# ziffy_board_v3.net
KiCad netlist of a schematic drawn in EAGLE
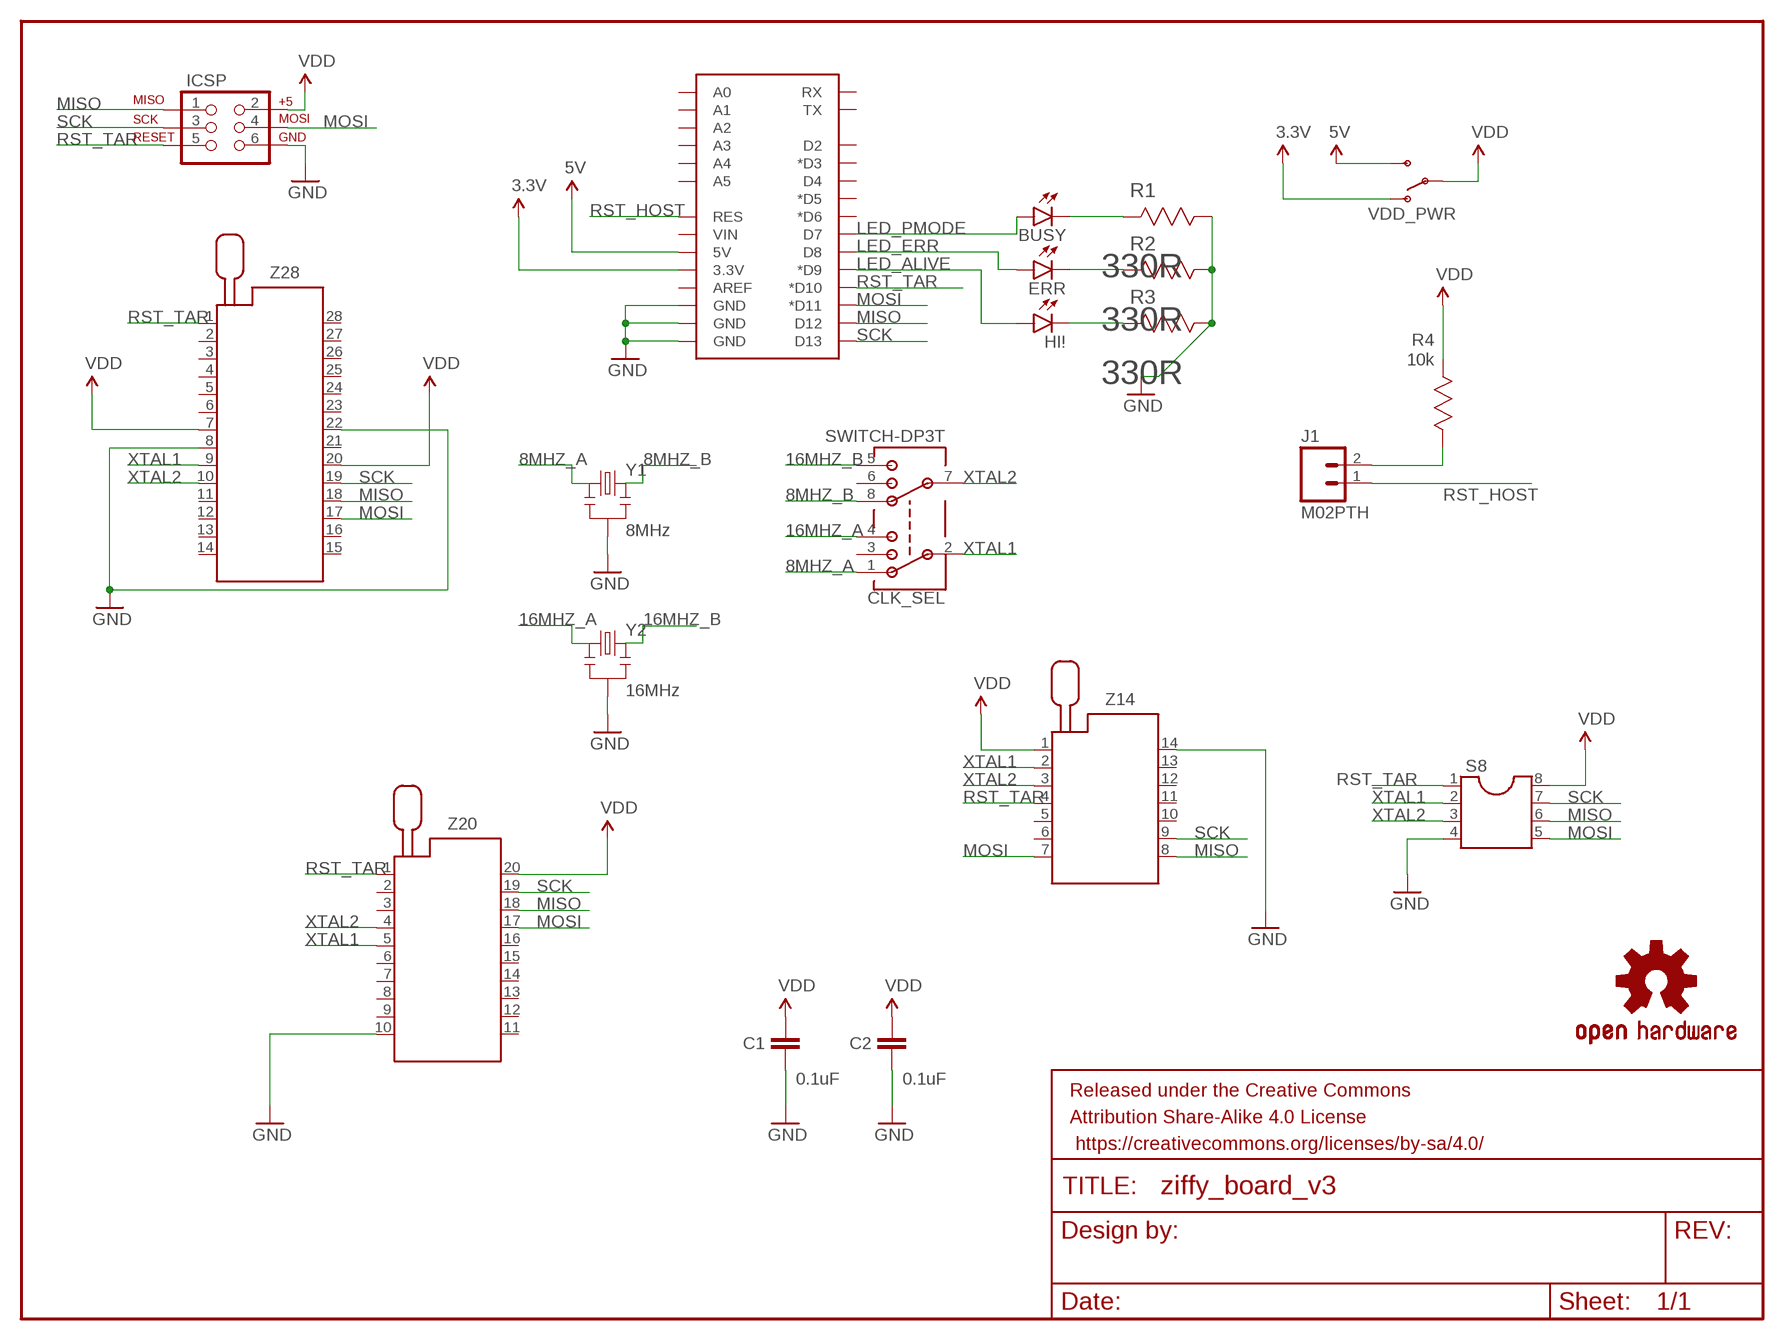
[diagram p0: schematic, sheet 1]

(export (version "E")
  (design (tool "Eeschema 10.0.6"))
  (components
    (comp (ref "BUSY")
      (value "YELLOW")
      (footprint "eagle-import:LED3MM")
      (libsource (lib "eagle-import") (part "LED3MM"))
    )
    (comp (ref "C1")
      (value "0.1uF")
      (footprint "eagle-import:CAP-PTH-SMALL2")
      (libsource (lib "eagle-import") (part "CAPPTH2"))
    )
    (comp (ref "C2")
      (value "0.1uF")
      (footprint "eagle-import:CAP-PTH-SMALL2")
      (libsource (lib "eagle-import") (part "CAPPTH2"))
    )
    (comp (ref "CLK_SEL")
      (value "SWITCH-DP3T")
      (footprint "eagle-import:SWITCH-DP3T")
      (libsource (lib "eagle-import") (part "SWITCH-DP3T"))
    )
    (comp (ref "ERR")
      (value "RED")
      (footprint "eagle-import:LED3MM")
      (libsource (lib "eagle-import") (part "LED3MM"))
    )
    (comp (ref "FRAME1")
      (value "FRAME-LETTER")
      (footprint "eagle-import:CREATIVE_COMMONS")
      (libsource (lib "eagle-import") (part "FRAME-LETTER"))
    )
    (comp (ref "HI!")
      (value "GREEN")
      (footprint "eagle-import:LED3MM")
      (libsource (lib "eagle-import") (part "LED3MM"))
    )
    (comp (ref "ICSP")
      (value "AVR_SPI_PRG_6PTH")
      (footprint "eagle-import:2X3")
      (libsource (lib "eagle-import") (part "AVR_SPI_PRG_6PTH"))
    )
    (comp (ref "J1")
      (value "M02PTH")
      (footprint "eagle-import:1X02")
      (libsource (lib "eagle-import") (part "M02PTH"))
    )
    (comp (ref "LOGO2")
      (value "OSHW-LOGOS")
      (footprint "eagle-import:OSHW-LOGO-S")
      (libsource (lib "eagle-import") (part "OSHW-LOGOS"))
    )
    (comp (ref "R1")
      (value "330R")
      (footprint "eagle-import:AXIAL-0.2")
      (libsource (lib "eagle-import") (part "RESISTOR_PTH_0.2"))
    )
    (comp (ref "R2")
      (value "330R")
      (footprint "eagle-import:AXIAL-0.2")
      (libsource (lib "eagle-import") (part "RESISTOR_PTH_0.2"))
    )
    (comp (ref "R3")
      (value "330R")
      (footprint "eagle-import:AXIAL-0.2")
      (libsource (lib "eagle-import") (part "RESISTOR_PTH_0.2"))
    )
    (comp (ref "R4")
      (value "10k")
      (footprint "eagle-import:AXIAL-0.2")
      (libsource (lib "eagle-import") (part "RESISTOR_PTH_0.2"))
    )
    (comp (ref "S8")
      (value "DIPSHIT")
      (footprint "eagle-import:DIL08")
      (libsource (lib "eagle-import") (part "DIL8"))
    )
    (comp (ref "U$1")
      (value "ARDUINO_SHIELDOUTLINE_NOHOLES")
      (footprint "eagle-import:ARDUINO_SHIELD_OUTLINE_NOHOLES")
      (libsource (lib "eagle-import") (part "ARDUINO_SHIELDOUTLINE_NOHOLES"))
    )
    (comp (ref "VDD_PWR")
      (value "SPDT")
      (footprint "eagle-import:SWITCH-SPDT")
      (libsource (lib "eagle-import") (part "SWITCH-SPDTPTH"))
    )
    (comp (ref "Y1")
      (value "8MHz")
      (footprint "eagle-import:RESONATOR-PTH")
      (libsource (lib "eagle-import") (part "RESONATORPTH"))
    )
    (comp (ref "Y2")
      (value "16MHz")
      (footprint "eagle-import:RESONATOR-PTH")
      (libsource (lib "eagle-import") (part "RESONATORPTH"))
    )
    (comp (ref "Z14")
      (value "ZIF14")
      (footprint "eagle-import:ZIF14")
      (fields (field (name "MF") "3M") (field (name "MPN") "214-3339-00-0602J"))
      (libsource (lib "eagle-import") (part "ZIF14"))
    )
    (comp (ref "Z20")
      (value "ZIF20")
      (footprint "eagle-import:ZIF20")
      (fields (field (name "MF") "3M") (field (name "MPN") "220-3342-00-0602J"))
      (libsource (lib "eagle-import") (part "ZIF20"))
    )
    (comp (ref "Z28")
      (value "ZIF28")
      (footprint "eagle-import:ZIF28")
      (libsource (lib "eagle-import") (part "ZIF28"))
    )
  )
  (nets
    (net (code "1") (name "/8MHZ_A") (class "Default")
      (node (ref "CLK_SEL") (pin "1") (pinfunction "1_1") (pintype "bidirectional"))
      (node (ref "Y1") (pin "1") (pinfunction "1_1") (pintype "passive"))
    )
    (net (code "2") (name "/8MHZ_B") (class "Default")
      (node (ref "CLK_SEL") (pin "8") (pinfunction "8_8") (pintype "bidirectional"))
      (node (ref "Y1") (pin "3") (pinfunction "3_3") (pintype "passive"))
    )
    (net (code "3") (name "/16MHZ_A") (class "Default")
      (node (ref "CLK_SEL") (pin "4") (pinfunction "4_4") (pintype "bidirectional"))
      (node (ref "Y2") (pin "1") (pinfunction "1_1") (pintype "passive"))
    )
    (net (code "4") (name "/16MHZ_B") (class "Default")
      (node (ref "CLK_SEL") (pin "5") (pinfunction "5_5") (pintype "bidirectional"))
      (node (ref "Y2") (pin "3") (pinfunction "3_3") (pintype "passive"))
    )
    (net (code "5") (name "/LED_ALIVE") (class "Default")
      (node (ref "HI!") (pin "A") (pinfunction "A_A") (pintype "passive"))
      (node (ref "U$1") (pin "D9") (pinfunction "*D9_D9") (pintype "bidirectional"))
    )
    (net (code "6") (name "/LED_ERR") (class "Default")
      (node (ref "ERR") (pin "A") (pinfunction "A_A") (pintype "passive"))
      (node (ref "U$1") (pin "D8") (pinfunction "D8_D8") (pintype "bidirectional"))
    )
    (net (code "7") (name "/LED_PMODE") (class "Default")
      (node (ref "BUSY") (pin "A") (pinfunction "A_A") (pintype "passive"))
      (node (ref "U$1") (pin "D7") (pinfunction "D7_D7") (pintype "bidirectional"))
    )
    (net (code "8") (name "/MISO") (class "Default")
      (node (ref "ICSP") (pin "1") (pinfunction "1_1") (pintype "passive"))
      (node (ref "S8") (pin "6") (pinfunction "6_6") (pintype "passive"))
      (node (ref "U$1") (pin "D12") (pinfunction "D12_D12") (pintype "bidirectional"))
      (node (ref "Z14") (pin "8") (pinfunction "8_8") (pintype "passive"))
      (node (ref "Z20") (pin "18") (pinfunction "18_18") (pintype "passive"))
      (node (ref "Z28") (pin "18") (pinfunction "18_18") (pintype "passive"))
    )
    (net (code "9") (name "/MOSI") (class "Default")
      (node (ref "ICSP") (pin "4") (pinfunction "4_4") (pintype "passive"))
      (node (ref "S8") (pin "5") (pinfunction "5_5") (pintype "passive"))
      (node (ref "U$1") (pin "D11") (pinfunction "*D11_D11") (pintype "bidirectional"))
      (node (ref "Z14") (pin "7") (pinfunction "7_7") (pintype "passive"))
      (node (ref "Z20") (pin "17") (pinfunction "17_17") (pintype "passive"))
      (node (ref "Z28") (pin "17") (pinfunction "17_17") (pintype "passive"))
    )
    (net (code "10") (name "/RST_HOST") (class "Default")
      (node (ref "J1") (pin "1") (pinfunction "1_1") (pintype "passive"))
      (node (ref "U$1") (pin "RES") (pinfunction "RES_RES") (pintype "bidirectional"))
    )
    (net (code "11") (name "/RST_TAR") (class "Default")
      (node (ref "ICSP") (pin "5") (pinfunction "5_5") (pintype "passive"))
      (node (ref "S8") (pin "1") (pinfunction "1_1") (pintype "passive"))
      (node (ref "U$1") (pin "D10") (pinfunction "*D10_D10") (pintype "bidirectional"))
      (node (ref "Z14") (pin "4") (pinfunction "4_4") (pintype "passive"))
      (node (ref "Z20") (pin "1") (pinfunction "1_1") (pintype "passive"))
      (node (ref "Z28") (pin "1") (pinfunction "1_1") (pintype "passive"))
    )
    (net (code "12") (name "/SCK") (class "Default")
      (node (ref "ICSP") (pin "3") (pinfunction "3_3") (pintype "passive"))
      (node (ref "S8") (pin "7") (pinfunction "7_7") (pintype "passive"))
      (node (ref "U$1") (pin "D13") (pinfunction "D13_D13") (pintype "bidirectional"))
      (node (ref "Z14") (pin "9") (pinfunction "9_9") (pintype "passive"))
      (node (ref "Z20") (pin "19") (pinfunction "19_19") (pintype "passive"))
      (node (ref "Z28") (pin "19") (pinfunction "19_19") (pintype "passive"))
    )
    (net (code "13") (name "/XTAL1") (class "Default")
      (node (ref "CLK_SEL") (pin "2") (pinfunction "2_2") (pintype "bidirectional"))
      (node (ref "S8") (pin "2") (pinfunction "2_2") (pintype "passive"))
      (node (ref "Z14") (pin "2") (pinfunction "2_2") (pintype "passive"))
      (node (ref "Z20") (pin "5") (pinfunction "5_5") (pintype "passive"))
      (node (ref "Z28") (pin "9") (pinfunction "9_9") (pintype "passive"))
    )
    (net (code "14") (name "/XTAL2") (class "Default")
      (node (ref "CLK_SEL") (pin "7") (pinfunction "7_7") (pintype "bidirectional"))
      (node (ref "S8") (pin "3") (pinfunction "3_3") (pintype "passive"))
      (node (ref "Z14") (pin "3") (pinfunction "3_3") (pintype "passive"))
      (node (ref "Z20") (pin "4") (pinfunction "4_4") (pintype "passive"))
      (node (ref "Z28") (pin "10") (pinfunction "10_10") (pintype "passive"))
    )
    (net (code "15") (name "3.3V") (class "Default")
      (node (ref "U$1") (pin "3.3V") (pinfunction "3.3V_3.3V") (pintype "bidirectional"))
      (node (ref "VDD_PWR") (pin "1") (pinfunction "O_1") (pintype "passive"))
    )
    (net (code "16") (name "5V") (class "Default")
      (node (ref "U$1") (pin "5V") (pinfunction "5V_5V") (pintype "bidirectional"))
      (node (ref "VDD_PWR") (pin "3") (pinfunction "S_3") (pintype "passive"))
    )
    (net (code "17") (name "GND") (class "Default")
      (node (ref "C1") (pin "2") (pinfunction "2_2") (pintype "passive"))
      (node (ref "C2") (pin "2") (pinfunction "2_2") (pintype "passive"))
      (node (ref "ICSP") (pin "6") (pinfunction "6_6") (pintype "passive"))
      (node (ref "R1") (pin "P$1") (pinfunction "2_P$1") (pintype "passive"))
      (node (ref "R2") (pin "P$1") (pinfunction "2_P$1") (pintype "passive"))
      (node (ref "R3") (pin "P$1") (pinfunction "2_P$1") (pintype "passive"))
      (node (ref "S8") (pin "4") (pinfunction "4_4") (pintype "passive"))
      (node (ref "U$1") (pin "GND@0") (pinfunction "GND_GND@0") (pintype "bidirectional"))
      (node (ref "U$1") (pin "GND@1") (pinfunction "GND_GND@1") (pintype "bidirectional"))
      (node (ref "U$1") (pin "GND@2") (pinfunction "GND_GND@2") (pintype "bidirectional"))
      (node (ref "Y1") (pin "2") (pinfunction "2_2") (pintype "passive"))
      (node (ref "Y2") (pin "2") (pinfunction "2_2") (pintype "passive"))
      (node (ref "Z14") (pin "14") (pinfunction "14_14") (pintype "passive"))
      (node (ref "Z20") (pin "10") (pinfunction "10_10") (pintype "passive"))
      (node (ref "Z28") (pin "22") (pinfunction "22_22") (pintype "passive"))
      (node (ref "Z28") (pin "8") (pinfunction "8_8") (pintype "passive"))
    )
    (net (code "18") (name "Net-(BUSY-C)") (class "Default")
      (node (ref "BUSY") (pin "K") (pinfunction "C_K") (pintype "passive"))
      (node (ref "R1") (pin "P$2") (pinfunction "1_P$2") (pintype "passive"))
    )
    (net (code "19") (name "Net-(ERR-C)") (class "Default")
      (node (ref "ERR") (pin "K") (pinfunction "C_K") (pintype "passive"))
      (node (ref "R2") (pin "P$2") (pinfunction "1_P$2") (pintype "passive"))
    )
    (net (code "20") (name "Net-(HI!-C)") (class "Default")
      (node (ref "HI!") (pin "K") (pinfunction "C_K") (pintype "passive"))
      (node (ref "R3") (pin "P$2") (pinfunction "1_P$2") (pintype "passive"))
    )
    (net (code "21") (name "Net-(R4-2)") (class "Default")
      (node (ref "J1") (pin "2") (pinfunction "2_2") (pintype "passive"))
      (node (ref "R4") (pin "P$1") (pinfunction "2_P$1") (pintype "passive"))
    )
    (net (code "22") (name "VDD") (class "Default")
      (node (ref "C1") (pin "1") (pinfunction "1_1") (pintype "passive"))
      (node (ref "C2") (pin "1") (pinfunction "1_1") (pintype "passive"))
      (node (ref "ICSP") (pin "2") (pinfunction "2_2") (pintype "passive"))
      (node (ref "R4") (pin "P$2") (pinfunction "1_P$2") (pintype "passive"))
      (node (ref "S8") (pin "8") (pinfunction "8_8") (pintype "passive"))
      (node (ref "VDD_PWR") (pin "2") (pinfunction "P_2") (pintype "passive"))
      (node (ref "Z14") (pin "1") (pinfunction "1_1") (pintype "passive"))
      (node (ref "Z20") (pin "20") (pinfunction "20_20") (pintype "passive"))
      (node (ref "Z28") (pin "20") (pinfunction "20_20") (pintype "passive"))
      (node (ref "Z28") (pin "7") (pinfunction "7_7") (pintype "passive"))
    )
    (net (code "23") (name "unconnected-(CLK_SEL-Pad3)") (class "Default")
      (node (ref "CLK_SEL") (pin "3") (pinfunction "3_3") (pintype "bidirectional"))
    )
    (net (code "24") (name "unconnected-(CLK_SEL-Pad6)") (class "Default")
      (node (ref "CLK_SEL") (pin "6") (pinfunction "6_6") (pintype "bidirectional"))
    )
    (net (code "25") (name "unconnected-(U$1-*D3-PadD3)") (class "Default")
      (node (ref "U$1") (pin "D3") (pinfunction "*D3_D3") (pintype "bidirectional"))
    )
    (net (code "26") (name "unconnected-(U$1-*D5-PadD5)") (class "Default")
      (node (ref "U$1") (pin "D5") (pinfunction "*D5_D5") (pintype "bidirectional"))
    )
    (net (code "27") (name "unconnected-(U$1-*D6-PadD6)") (class "Default")
      (node (ref "U$1") (pin "D6") (pinfunction "*D6_D6") (pintype "bidirectional"))
    )
    (net (code "28") (name "unconnected-(U$1-PadA0)") (class "Default")
      (node (ref "U$1") (pin "A0") (pinfunction "A0_A0") (pintype "bidirectional"))
    )
    (net (code "29") (name "unconnected-(U$1-PadA1)") (class "Default")
      (node (ref "U$1") (pin "A1") (pinfunction "A1_A1") (pintype "bidirectional"))
    )
    (net (code "30") (name "unconnected-(U$1-PadA2)") (class "Default")
      (node (ref "U$1") (pin "A2") (pinfunction "A2_A2") (pintype "bidirectional"))
    )
    (net (code "31") (name "unconnected-(U$1-PadA3)") (class "Default")
      (node (ref "U$1") (pin "A3") (pinfunction "A3_A3") (pintype "bidirectional"))
    )
    (net (code "32") (name "unconnected-(U$1-PadA4)") (class "Default")
      (node (ref "U$1") (pin "A4") (pinfunction "A4_A4") (pintype "bidirectional"))
    )
    (net (code "33") (name "unconnected-(U$1-PadA5)") (class "Default")
      (node (ref "U$1") (pin "A5") (pinfunction "A5_A5") (pintype "bidirectional"))
    )
    (net (code "34") (name "unconnected-(U$1-PadAREF)") (class "Default")
      (node (ref "U$1") (pin "AREF") (pinfunction "AREF_AREF") (pintype "bidirectional"))
    )
    (net (code "35") (name "unconnected-(U$1-PadD2)") (class "Default")
      (node (ref "U$1") (pin "D2") (pinfunction "D2_D2") (pintype "bidirectional"))
    )
    (net (code "36") (name "unconnected-(U$1-PadD4)") (class "Default")
      (node (ref "U$1") (pin "D4") (pinfunction "D4_D4") (pintype "bidirectional"))
    )
    (net (code "37") (name "unconnected-(U$1-PadRX)") (class "Default")
      (node (ref "U$1") (pin "RX") (pinfunction "RX_RX") (pintype "bidirectional"))
    )
    (net (code "38") (name "unconnected-(U$1-PadTX)") (class "Default")
      (node (ref "U$1") (pin "TX") (pinfunction "TX_TX") (pintype "bidirectional"))
    )
    (net (code "39") (name "unconnected-(U$1-PadVIN)") (class "Default")
      (node (ref "U$1") (pin "VIN") (pinfunction "VIN_VIN") (pintype "bidirectional"))
    )
    (net (code "40") (name "unconnected-(Z14-Pad5)") (class "Default")
      (node (ref "Z14") (pin "5") (pinfunction "5_5") (pintype "passive"))
    )
    (net (code "41") (name "unconnected-(Z14-Pad6)") (class "Default")
      (node (ref "Z14") (pin "6") (pinfunction "6_6") (pintype "passive"))
    )
    (net (code "42") (name "unconnected-(Z14-Pad10)") (class "Default")
      (node (ref "Z14") (pin "10") (pinfunction "10_10") (pintype "passive"))
    )
    (net (code "43") (name "unconnected-(Z14-Pad11)") (class "Default")
      (node (ref "Z14") (pin "11") (pinfunction "11_11") (pintype "passive"))
    )
    (net (code "44") (name "unconnected-(Z14-Pad12)") (class "Default")
      (node (ref "Z14") (pin "12") (pinfunction "12_12") (pintype "passive"))
    )
    (net (code "45") (name "unconnected-(Z14-Pad13)") (class "Default")
      (node (ref "Z14") (pin "13") (pinfunction "13_13") (pintype "passive"))
    )
    (net (code "46") (name "unconnected-(Z20-Pad2)") (class "Default")
      (node (ref "Z20") (pin "2") (pinfunction "2_2") (pintype "passive"))
    )
    (net (code "47") (name "unconnected-(Z20-Pad3)") (class "Default")
      (node (ref "Z20") (pin "3") (pinfunction "3_3") (pintype "passive"))
    )
    (net (code "48") (name "unconnected-(Z20-Pad6)") (class "Default")
      (node (ref "Z20") (pin "6") (pinfunction "6_6") (pintype "passive"))
    )
    (net (code "49") (name "unconnected-(Z20-Pad7)") (class "Default")
      (node (ref "Z20") (pin "7") (pinfunction "7_7") (pintype "passive"))
    )
    (net (code "50") (name "unconnected-(Z20-Pad8)") (class "Default")
      (node (ref "Z20") (pin "8") (pinfunction "8_8") (pintype "passive"))
    )
    (net (code "51") (name "unconnected-(Z20-Pad9)") (class "Default")
      (node (ref "Z20") (pin "9") (pinfunction "9_9") (pintype "passive"))
    )
    (net (code "52") (name "unconnected-(Z20-Pad11)") (class "Default")
      (node (ref "Z20") (pin "11") (pinfunction "11_11") (pintype "passive"))
    )
    (net (code "53") (name "unconnected-(Z20-Pad12)") (class "Default")
      (node (ref "Z20") (pin "12") (pinfunction "12_12") (pintype "passive"))
    )
    (net (code "54") (name "unconnected-(Z20-Pad13)") (class "Default")
      (node (ref "Z20") (pin "13") (pinfunction "13_13") (pintype "passive"))
    )
    (net (code "55") (name "unconnected-(Z20-Pad14)") (class "Default")
      (node (ref "Z20") (pin "14") (pinfunction "14_14") (pintype "passive"))
    )
    (net (code "56") (name "unconnected-(Z20-Pad15)") (class "Default")
      (node (ref "Z20") (pin "15") (pinfunction "15_15") (pintype "passive"))
    )
    (net (code "57") (name "unconnected-(Z20-Pad16)") (class "Default")
      (node (ref "Z20") (pin "16") (pinfunction "16_16") (pintype "passive"))
    )
    (net (code "58") (name "unconnected-(Z28-Pad2)") (class "Default")
      (node (ref "Z28") (pin "2") (pinfunction "2_2") (pintype "passive"))
    )
    (net (code "59") (name "unconnected-(Z28-Pad3)") (class "Default")
      (node (ref "Z28") (pin "3") (pinfunction "3_3") (pintype "passive"))
    )
    (net (code "60") (name "unconnected-(Z28-Pad4)") (class "Default")
      (node (ref "Z28") (pin "4") (pinfunction "4_4") (pintype "passive"))
    )
    (net (code "61") (name "unconnected-(Z28-Pad5)") (class "Default")
      (node (ref "Z28") (pin "5") (pinfunction "5_5") (pintype "passive"))
    )
    (net (code "62") (name "unconnected-(Z28-Pad6)") (class "Default")
      (node (ref "Z28") (pin "6") (pinfunction "6_6") (pintype "passive"))
    )
    (net (code "63") (name "unconnected-(Z28-Pad11)") (class "Default")
      (node (ref "Z28") (pin "11") (pinfunction "11_11") (pintype "passive"))
    )
    (net (code "64") (name "unconnected-(Z28-Pad12)") (class "Default")
      (node (ref "Z28") (pin "12") (pinfunction "12_12") (pintype "passive"))
    )
    (net (code "65") (name "unconnected-(Z28-Pad13)") (class "Default")
      (node (ref "Z28") (pin "13") (pinfunction "13_13") (pintype "passive"))
    )
    (net (code "66") (name "unconnected-(Z28-Pad14)") (class "Default")
      (node (ref "Z28") (pin "14") (pinfunction "14_14") (pintype "passive"))
    )
    (net (code "67") (name "unconnected-(Z28-Pad15)") (class "Default")
      (node (ref "Z28") (pin "15") (pinfunction "15_15") (pintype "passive"))
    )
    (net (code "68") (name "unconnected-(Z28-Pad16)") (class "Default")
      (node (ref "Z28") (pin "16") (pinfunction "16_16") (pintype "passive"))
    )
    (net (code "69") (name "unconnected-(Z28-Pad21)") (class "Default")
      (node (ref "Z28") (pin "21") (pinfunction "21_21") (pintype "passive"))
    )
    (net (code "70") (name "unconnected-(Z28-Pad23)") (class "Default")
      (node (ref "Z28") (pin "23") (pinfunction "23_23") (pintype "passive"))
    )
    (net (code "71") (name "unconnected-(Z28-Pad24)") (class "Default")
      (node (ref "Z28") (pin "24") (pinfunction "24_24") (pintype "passive"))
    )
    (net (code "72") (name "unconnected-(Z28-Pad25)") (class "Default")
      (node (ref "Z28") (pin "25") (pinfunction "25_25") (pintype "passive"))
    )
    (net (code "73") (name "unconnected-(Z28-Pad26)") (class "Default")
      (node (ref "Z28") (pin "26") (pinfunction "26_26") (pintype "passive"))
    )
    (net (code "74") (name "unconnected-(Z28-Pad27)") (class "Default")
      (node (ref "Z28") (pin "27") (pinfunction "27_27") (pintype "passive"))
    )
    (net (code "75") (name "unconnected-(Z28-Pad28)") (class "Default")
      (node (ref "Z28") (pin "28") (pinfunction "28_28") (pintype "passive"))
    )
  )
)
